# Maduino_Zero_Bluetooth_4_0_HM-13_v1_0.net
KiCad netlist of a schematic drawn in EAGLE
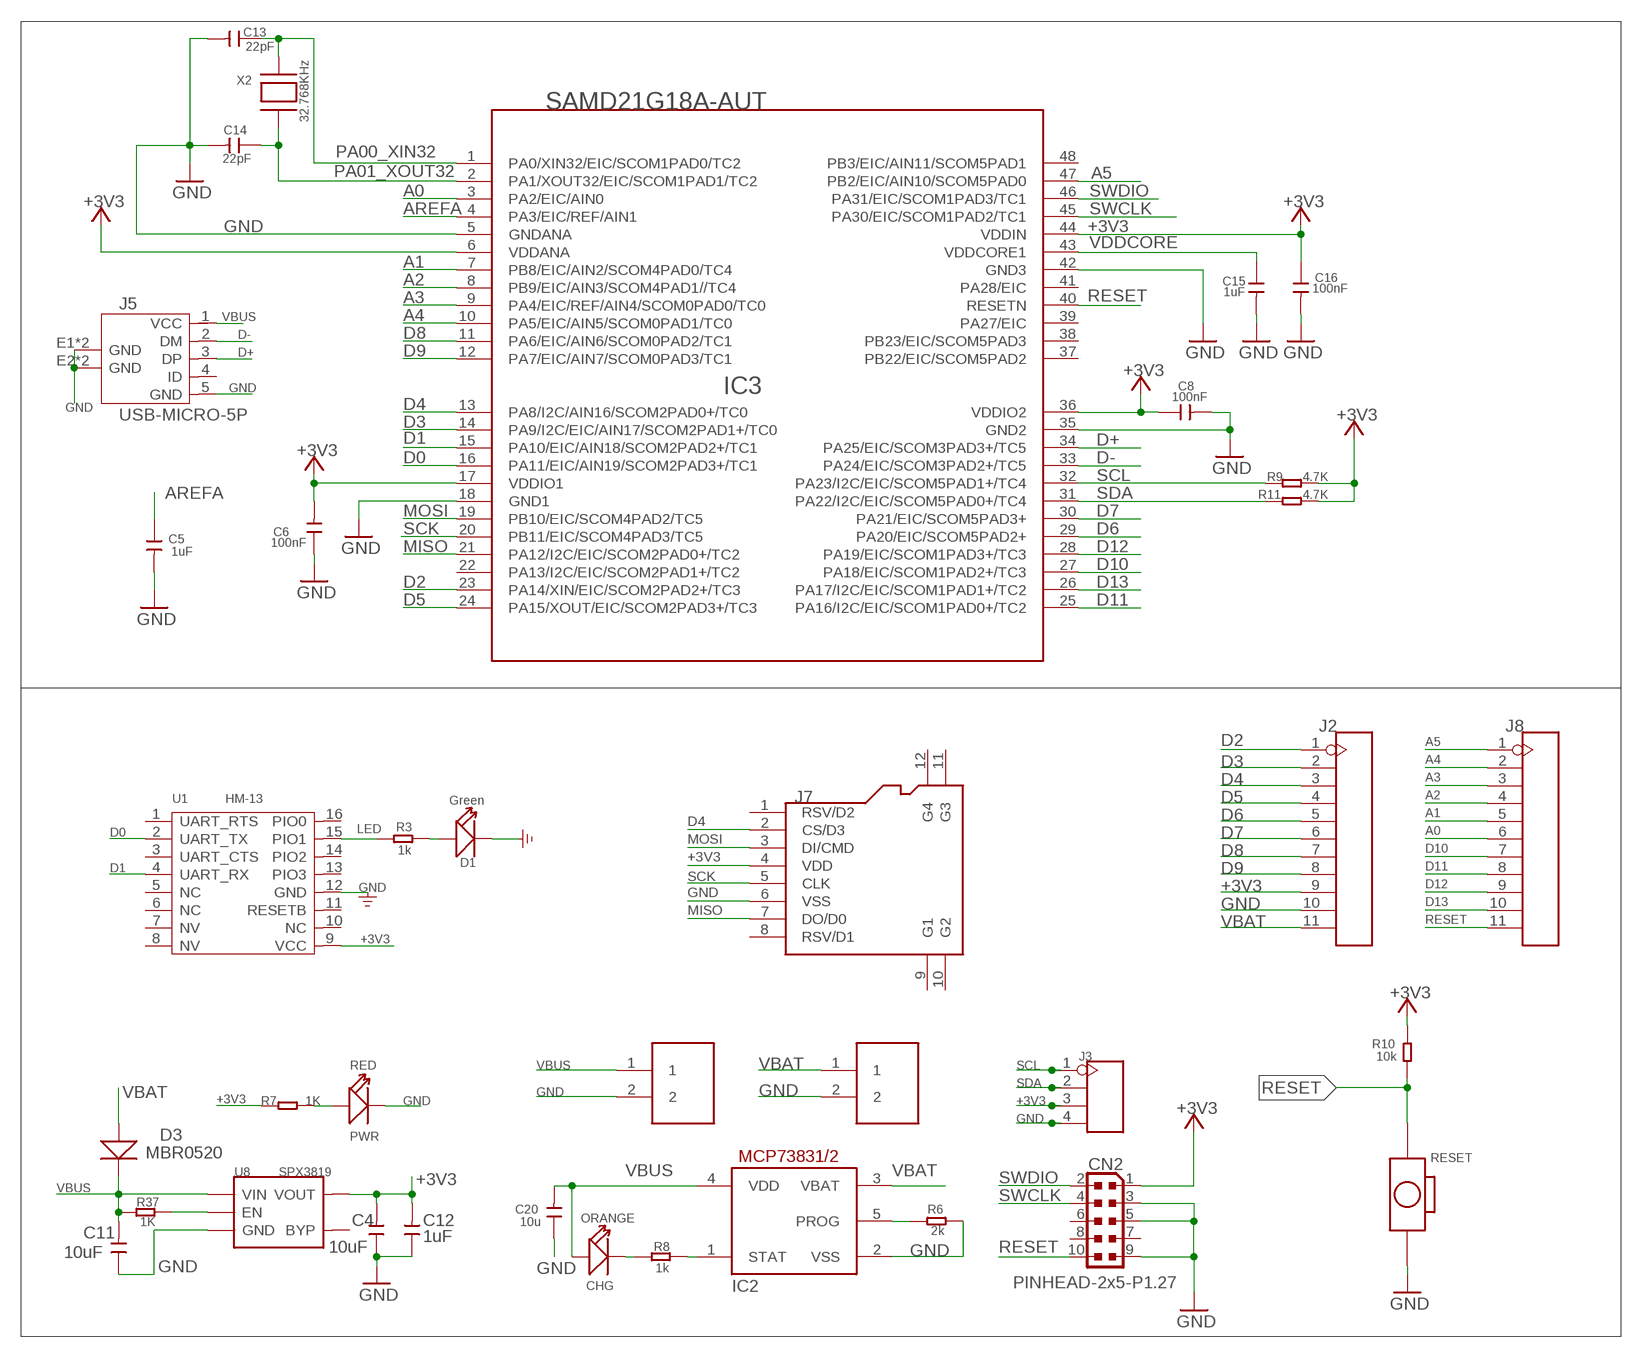
[diagram p0: schematic, sheet 1]

(export (version "E")
  (design (tool "Eeschema 10.0.6"))
  (components
    (comp (ref "C4")
      (value "10uF")
      (footprint "eagle-import:0603")
      (libsource (lib "eagle-import") (part "C-0603"))
    )
    (comp (ref "C5")
      (value "1uF")
      (footprint "eagle-import:0603")
      (libsource (lib "eagle-import") (part "C-0603"))
    )
    (comp (ref "C6")
      (value "100nF")
      (footprint "eagle-import:0603")
      (libsource (lib "eagle-import") (part "C-0603"))
    )
    (comp (ref "C8")
      (value "100nF")
      (footprint "eagle-import:0603")
      (libsource (lib "eagle-import") (part "C-0603"))
    )
    (comp (ref "C11")
      (value "10uF")
      (footprint "eagle-import:0603")
      (libsource (lib "eagle-import") (part "C-0603"))
    )
    (comp (ref "C12")
      (value "1uF")
      (footprint "eagle-import:0603")
      (libsource (lib "eagle-import") (part "C-0603"))
    )
    (comp (ref "C13")
      (value "22pF")
      (footprint "eagle-import:0603")
      (libsource (lib "eagle-import") (part "C-0603"))
    )
    (comp (ref "C14")
      (value "22pF")
      (footprint "eagle-import:0603")
      (libsource (lib "eagle-import") (part "C-0603"))
    )
    (comp (ref "C15")
      (value "1uF")
      (footprint "eagle-import:0603")
      (libsource (lib "eagle-import") (part "C-0603"))
    )
    (comp (ref "C16")
      (value "100nF")
      (footprint "eagle-import:0603")
      (libsource (lib "eagle-import") (part "C-0603"))
    )
    (comp (ref "C20")
      (value "10u")
      (footprint "eagle-import:0603")
      (libsource (lib "eagle-import") (part "C-0603"))
    )
    (comp (ref "CHG")
      (value "ORANGE")
      (footprint "eagle-import:D0603")
      (libsource (lib "eagle-import") (part "007-LED0603"))
    )
    (comp (ref "CN2")
      (value "PINHEAD-2x5-P1.27")
      (footprint "eagle-import:PINHEAD_2X05_127")
      (libsource (lib "eagle-import") (part "0171_PH127-205DF055G00AROUND-PADS"))
    )
    (comp (ref "D1")
      (value "Green")
      (footprint "eagle-import:LED-0603")
      (libsource (lib "eagle-import") (part "LED'0603'"))
    )
    (comp (ref "D3")
      (value "MBR0520")
      (footprint "eagle-import:SOD123")
      (libsource (lib "eagle-import") (part "D'1206'"))
    )
    (comp (ref "IC2")
      (value "MCP73831/OT")
      (footprint "eagle-import:SOT23-5L")
      (libsource (lib "eagle-import") (part "MCP73831/OT"))
    )
    (comp (ref "IC3")
      (value "SAMD21G18A-AUT")
      (footprint "eagle-import:TQFP48-7X7")
      (libsource (lib "eagle-import") (part "ATSAMD21G18A-AUT"))
    )
    (comp (ref "J1")
      (value "PH2.0-2P-90-DIP")
      (footprint "eagle-import:PH2.0-2P-90-DIP")
      (libsource (lib "eagle-import") (part "PH2.0-2P-90-DIP"))
    )
    (comp (ref "J2")
      (value "HEADER-11P-2.54")
      (footprint "eagle-import:11P-2.54")
      (libsource (lib "eagle-import") (part "HEADER-11P-2.54"))
    )
    (comp (ref "J3")
      (value "HEADER-4P-60/35MILROUND")
      (footprint "eagle-import:4P-65_35ROUND")
      (libsource (lib "eagle-import") (part "HEADER-4P-60/35MILROUND"))
    )
    (comp (ref "J5")
      (value "USB-MICRO-5P")
      (footprint "eagle-import:MICRO-USB-5P")
      (libsource (lib "eagle-import") (part "USB-MICRO-5P"))
    )
    (comp (ref "J6")
      (value "PH2.0-2P-90-DIP")
      (footprint "eagle-import:PH2.0-2P-90-DIP")
      (libsource (lib "eagle-import") (part "PH2.0-2P-90-DIP"))
    )
    (comp (ref "J7")
      (value "HOLDER-MICROSD-8P")
      (footprint "eagle-import:8P-SMD")
      (libsource (lib "eagle-import") (part "HOLDER-MICROSD-8P"))
    )
    (comp (ref "J8")
      (value "HEADER-11P-2.54")
      (footprint "eagle-import:11P-2.54")
      (libsource (lib "eagle-import") (part "HEADER-11P-2.54"))
    )
    (comp (ref "PWR")
      (value "RED")
      (footprint "eagle-import:LED-0603")
      (libsource (lib "eagle-import") (part "LED'0603'"))
    )
    (comp (ref "R3")
      (value "1k")
      (footprint "eagle-import:R0603")
      (libsource (lib "eagle-import") (part "R-0603"))
    )
    (comp (ref "R6")
      (value "2k")
      (footprint "eagle-import:R0603")
      (libsource (lib "eagle-import") (part "R-0603"))
    )
    (comp (ref "R7")
      (value "1K")
      (footprint "eagle-import:R0603")
      (libsource (lib "eagle-import") (part "R-0603"))
    )
    (comp (ref "R8")
      (value "1k")
      (footprint "eagle-import:R0603")
      (libsource (lib "eagle-import") (part "R-0603"))
    )
    (comp (ref "R9")
      (value "4.7K")
      (footprint "eagle-import:R0603")
      (libsource (lib "eagle-import") (part "R-0603"))
    )
    (comp (ref "R10")
      (value "10k")
      (footprint "eagle-import:R0603")
      (libsource (lib "eagle-import") (part "R-0603"))
    )
    (comp (ref "R11")
      (value "4.7K")
      (footprint "eagle-import:R0603")
      (libsource (lib "eagle-import") (part "R-0603"))
    )
    (comp (ref "R37")
      (value "1K")
      (footprint "eagle-import:R0603")
      (libsource (lib "eagle-import") (part "R-0603"))
    )
    (comp (ref "RESET")
      (value "BOTTON-2P-90D")
      (footprint "eagle-import:2P-7.62X3.56-90D")
      (libsource (lib "eagle-import") (part "BOTTON-2P-90D"))
    )
    (comp (ref "U1")
      (value "HM-13")
      (footprint "eagle-import:16P-18.5X13.5X0.8")
      (libsource (lib "eagle-import") (part "HM-11"))
    )
    (comp (ref "U8")
      (value "SPX3819")
      (footprint "eagle-import:SOT23-5")
      (libsource (lib "eagle-import") (part "SPX3819"))
    )
    (comp (ref "X2")
      (value "32.768KHz")
      (footprint "eagle-import:XTAL3215")
      (libsource (lib "eagle-import") (part "XTAL-3.2X1.5"))
    )
  )
  (nets
    (net (code "1") (name "+3V3") (class "Default")
      (node (ref "C12") (pin "2") (pinfunction "2_2") (pintype "passive"))
      (node (ref "C16") (pin "1") (pinfunction "1_1") (pintype "passive"))
      (node (ref "C4") (pin "2") (pinfunction "2_2") (pintype "passive"))
      (node (ref "C6") (pin "2") (pinfunction "2_2") (pintype "passive"))
      (node (ref "C8") (pin "1") (pinfunction "1_1") (pintype "passive"))
      (node (ref "CN2") (pin "1") (pinfunction "1_1") (pintype "passive"))
      (node (ref "IC3") (pin "17") (pinfunction "VDDIO1_17") (pintype "power_in"))
      (node (ref "IC3") (pin "36") (pinfunction "VDDIO2_36") (pintype "power_in"))
      (node (ref "IC3") (pin "44") (pinfunction "VDDIN_44") (pintype "power_in"))
      (node (ref "IC3") (pin "6") (pinfunction "VDDANA_6") (pintype "power_in"))
      (node (ref "J2") (pin "9") (pinfunction "9_9") (pintype "bidirectional"))
      (node (ref "J3") (pin "3") (pinfunction "P$3_3") (pintype "bidirectional"))
      (node (ref "J7") (pin "4") (pinfunction "VDD_4") (pintype "bidirectional"))
      (node (ref "R10") (pin "2") (pinfunction "2_2") (pintype "passive"))
      (node (ref "R11") (pin "2") (pinfunction "2_2") (pintype "passive"))
      (node (ref "R7") (pin "1") (pinfunction "1_1") (pintype "passive"))
      (node (ref "R9") (pin "2") (pinfunction "2_2") (pintype "passive"))
      (node (ref "U1") (pin "9") (pinfunction "VCC_9") (pintype "bidirectional"))
      (node (ref "U8") (pin "5") (pinfunction "VOUT_5") (pintype "bidirectional"))
    )
    (net (code "2") (name "/A0") (class "Default")
      (node (ref "IC3") (pin "3") (pinfunction "PA2/EIC/AIN0_3") (pintype "bidirectional"))
      (node (ref "J8") (pin "6") (pinfunction "6_6") (pintype "bidirectional"))
    )
    (net (code "3") (name "/A1") (class "Default")
      (node (ref "IC3") (pin "7") (pinfunction "PB8/EIC/AIN2/SCOM4PAD0/TC4_7") (pintype "bidirectional"))
      (node (ref "J8") (pin "5") (pinfunction "5_5") (pintype "bidirectional"))
    )
    (net (code "4") (name "/A2") (class "Default")
      (node (ref "IC3") (pin "8") (pinfunction "PB9/EIC/AIN3/SCOM4PAD1//TC4_8") (pintype "bidirectional"))
      (node (ref "J8") (pin "4") (pinfunction "4_4") (pintype "bidirectional"))
    )
    (net (code "5") (name "/A3") (class "Default")
      (node (ref "IC3") (pin "9") (pinfunction "PA4/EIC/REF/AIN4/SCOM0PAD0/TC0_9") (pintype "bidirectional"))
      (node (ref "J8") (pin "3") (pinfunction "3_3") (pintype "bidirectional"))
    )
    (net (code "6") (name "/A4") (class "Default")
      (node (ref "IC3") (pin "10") (pinfunction "PA5/EIC/AIN5/SCOM0PAD1/TC0_10") (pintype "bidirectional"))
      (node (ref "J8") (pin "2") (pinfunction "2_2") (pintype "bidirectional"))
    )
    (net (code "7") (name "/A5") (class "Default")
      (node (ref "IC3") (pin "47") (pinfunction "PB2/EIC/AIN10/SCOM5PAD0_47") (pintype "bidirectional"))
      (node (ref "J8") (pin "1") (pinfunction "1_1") (pintype "bidirectional"))
    )
    (net (code "8") (name "/AREFA") (class "Default")
      (node (ref "C5") (pin "1") (pinfunction "1_1") (pintype "passive"))
      (node (ref "IC3") (pin "4") (pinfunction "PA3/EIC/REF/AIN1_4") (pintype "bidirectional"))
    )
    (net (code "9") (name "/D+") (class "Default")
      (node (ref "IC3") (pin "34") (pinfunction "PA25/EIC/SCOM3PAD3+/TC5_34") (pintype "bidirectional"))
      (node (ref "J5") (pin "3") (pinfunction "DP_3") (pintype "bidirectional"))
    )
    (net (code "10") (name "/D-") (class "Default")
      (node (ref "IC3") (pin "33") (pinfunction "PA24/EIC/SCOM3PAD2+/TC5_33") (pintype "bidirectional"))
      (node (ref "J5") (pin "2") (pinfunction "DM_2") (pintype "bidirectional"))
    )
    (net (code "11") (name "/D0") (class "Default")
      (node (ref "IC3") (pin "16") (pinfunction "PA11/EIC/AIN19/SCOM2PAD3+/TC1_16") (pintype "bidirectional"))
      (node (ref "U1") (pin "2") (pinfunction "UART_TX_2") (pintype "bidirectional"))
    )
    (net (code "12") (name "/D1") (class "Default")
      (node (ref "IC3") (pin "15") (pinfunction "PA10/EIC/AIN18/SCOM2PAD2+/TC1_15") (pintype "bidirectional"))
      (node (ref "U1") (pin "4") (pinfunction "UART_RX_4") (pintype "bidirectional"))
    )
    (net (code "13") (name "/D2") (class "Default")
      (node (ref "IC3") (pin "23") (pinfunction "PA14/XIN/EIC/SCOM2PAD2+/TC3_23") (pintype "bidirectional"))
      (node (ref "J2") (pin "1") (pinfunction "1_1") (pintype "bidirectional"))
    )
    (net (code "14") (name "/D3") (class "Default")
      (node (ref "IC3") (pin "14") (pinfunction "PA9/I2C/EIC/AIN17/SCOM2PAD1+/TC0_14") (pintype "bidirectional"))
      (node (ref "J2") (pin "2") (pinfunction "2_2") (pintype "bidirectional"))
    )
    (net (code "15") (name "/D4") (class "Default")
      (node (ref "IC3") (pin "13") (pinfunction "PA8/I2C/AIN16/SCOM2PAD0+/TC0_13") (pintype "bidirectional"))
      (node (ref "J2") (pin "3") (pinfunction "3_3") (pintype "bidirectional"))
      (node (ref "J7") (pin "2") (pinfunction "CS/D3_2") (pintype "bidirectional"))
    )
    (net (code "16") (name "/D5") (class "Default")
      (node (ref "IC3") (pin "24") (pinfunction "PA15/XOUT/EIC/SCOM2PAD3+/TC3_24") (pintype "bidirectional"))
      (node (ref "J2") (pin "4") (pinfunction "4_4") (pintype "bidirectional"))
    )
    (net (code "17") (name "/D6") (class "Default")
      (node (ref "IC3") (pin "29") (pinfunction "PA20/EIC/SCOM5PAD2+_29") (pintype "bidirectional"))
      (node (ref "J2") (pin "5") (pinfunction "5_5") (pintype "bidirectional"))
    )
    (net (code "18") (name "/D7") (class "Default")
      (node (ref "IC3") (pin "30") (pinfunction "PA21/EIC/SCOM5PAD3+_30") (pintype "bidirectional"))
      (node (ref "J2") (pin "6") (pinfunction "6_6") (pintype "bidirectional"))
    )
    (net (code "19") (name "/D8") (class "Default")
      (node (ref "IC3") (pin "11") (pinfunction "PA6/EIC/AIN6/SCOM0PAD2/TC1_11") (pintype "bidirectional"))
      (node (ref "J2") (pin "7") (pinfunction "7_7") (pintype "bidirectional"))
    )
    (net (code "20") (name "/D9") (class "Default")
      (node (ref "IC3") (pin "12") (pinfunction "PA7/EIC/AIN7/SCOM0PAD3/TC1_12") (pintype "bidirectional"))
      (node (ref "J2") (pin "8") (pinfunction "8_8") (pintype "bidirectional"))
    )
    (net (code "21") (name "/D10") (class "Default")
      (node (ref "IC3") (pin "27") (pinfunction "PA18/EIC/SCOM1PAD2+/TC3_27") (pintype "bidirectional"))
      (node (ref "J8") (pin "7") (pinfunction "7_7") (pintype "bidirectional"))
    )
    (net (code "22") (name "/D11") (class "Default")
      (node (ref "IC3") (pin "25") (pinfunction "PA16/I2C/EIC/SCOM1PAD0+/TC2_25") (pintype "bidirectional"))
      (node (ref "J8") (pin "8") (pinfunction "8_8") (pintype "bidirectional"))
    )
    (net (code "23") (name "/D12") (class "Default")
      (node (ref "IC3") (pin "28") (pinfunction "PA19/EIC/SCOM1PAD3+/TC3_28") (pintype "bidirectional"))
      (node (ref "J8") (pin "9") (pinfunction "9_9") (pintype "bidirectional"))
    )
    (net (code "24") (name "/D13") (class "Default")
      (node (ref "IC3") (pin "26") (pinfunction "PA17/I2C/EIC/SCOM1PAD1+/TC2_26") (pintype "bidirectional"))
      (node (ref "J8") (pin "10") (pinfunction "10_10") (pintype "bidirectional"))
    )
    (net (code "25") (name "/LED") (class "Default")
      (node (ref "R3") (pin "1") (pinfunction "1_1") (pintype "passive"))
      (node (ref "U1") (pin "15") (pinfunction "PIO1_15") (pintype "bidirectional"))
    )
    (net (code "26") (name "/MISO") (class "Default")
      (node (ref "IC3") (pin "21") (pinfunction "PA12/I2C/EIC/SCOM2PAD0+/TC2_21") (pintype "bidirectional"))
      (node (ref "J7") (pin "7") (pinfunction "DO/D0_7") (pintype "bidirectional"))
    )
    (net (code "27") (name "/MOSI") (class "Default")
      (node (ref "IC3") (pin "19") (pinfunction "PB10/EIC/SCOM4PAD2/TC5_19") (pintype "bidirectional"))
      (node (ref "J7") (pin "3") (pinfunction "DI/CMD_3") (pintype "bidirectional"))
    )
    (net (code "28") (name "/PA00_XIN32") (class "Default")
      (node (ref "C13") (pin "1") (pinfunction "1_1") (pintype "passive"))
      (node (ref "IC3") (pin "1") (pinfunction "PA0/XIN32/EIC/SCOM1PAD0/TC2_1") (pintype "bidirectional"))
      (node (ref "X2") (pin "P$2") (pinfunction "P$2_P$2") (pintype "bidirectional"))
    )
    (net (code "29") (name "/PA01_XOUT32") (class "Default")
      (node (ref "C14") (pin "1") (pinfunction "1_1") (pintype "passive"))
      (node (ref "IC3") (pin "2") (pinfunction "PA1/XOUT32/EIC/SCOM1PAD1/TC2_2") (pintype "bidirectional"))
      (node (ref "X2") (pin "P$1") (pinfunction "P$1_P$1") (pintype "bidirectional"))
    )
    (net (code "30") (name "/SCK") (class "Default")
      (node (ref "IC3") (pin "20") (pinfunction "PB11/EIC/SCOM4PAD3/TC5_20") (pintype "bidirectional"))
      (node (ref "J7") (pin "5") (pinfunction "CLK_5") (pintype "bidirectional"))
    )
    (net (code "31") (name "/SCL") (class "Default")
      (node (ref "IC3") (pin "32") (pinfunction "PA23/I2C/EIC/SCOM5PAD1+/TC4_32") (pintype "bidirectional"))
      (node (ref "J3") (pin "1") (pinfunction "P$1_1") (pintype "bidirectional"))
      (node (ref "R9") (pin "1") (pinfunction "1_1") (pintype "passive"))
    )
    (net (code "32") (name "/SDA") (class "Default")
      (node (ref "IC3") (pin "31") (pinfunction "PA22/I2C/EIC/SCOM5PAD0+/TC4_31") (pintype "bidirectional"))
      (node (ref "J3") (pin "2") (pinfunction "P$2_2") (pintype "bidirectional"))
      (node (ref "R11") (pin "1") (pinfunction "1_1") (pintype "passive"))
    )
    (net (code "33") (name "/SWCLK") (class "Default")
      (node (ref "CN2") (pin "4") (pinfunction "4_4") (pintype "passive"))
      (node (ref "IC3") (pin "45") (pinfunction "PA30/EIC/SCOM1PAD2/TC1_45") (pintype "bidirectional"))
    )
    (net (code "34") (name "/SWDIO") (class "Default")
      (node (ref "CN2") (pin "2") (pinfunction "2_2") (pintype "passive"))
      (node (ref "IC3") (pin "46") (pinfunction "PA31/EIC/SCOM1PAD3/TC1_46") (pintype "bidirectional"))
    )
    (net (code "35") (name "/VBAT") (class "Default")
      (node (ref "D3") (pin "+") (pinfunction "+_+") (pintype "passive"))
      (node (ref "IC2") (pin "3") (pinfunction "VBAT_3") (pintype "bidirectional"))
      (node (ref "J2") (pin "11") (pinfunction "11_11") (pintype "bidirectional"))
      (node (ref "J6") (pin "1") (pinfunction "1_1") (pintype "bidirectional"))
    )
    (net (code "36") (name "/VBUS") (class "Default")
      (node (ref "C11") (pin "2") (pinfunction "2_2") (pintype "passive"))
      (node (ref "C20") (pin "2") (pinfunction "2_2") (pintype "passive"))
      (node (ref "CHG") (pin "+") (pinfunction "+_+") (pintype "passive"))
      (node (ref "D3") (pin "-") (pinfunction "-_-") (pintype "passive"))
      (node (ref "IC2") (pin "4") (pinfunction "VDD_4") (pintype "power_in"))
      (node (ref "J1") (pin "1") (pinfunction "1_1") (pintype "bidirectional"))
      (node (ref "J5") (pin "1") (pinfunction "VCC_1") (pintype "bidirectional"))
      (node (ref "R37") (pin "1") (pinfunction "1_1") (pintype "passive"))
      (node (ref "U8") (pin "1") (pinfunction "VIN_1") (pintype "bidirectional"))
    )
    (net (code "37") (name "/VDDCORE") (class "Default")
      (node (ref "C15") (pin "1") (pinfunction "1_1") (pintype "passive"))
      (node (ref "IC3") (pin "43") (pinfunction "VDDCORE1_43") (pintype "input"))
    )
    (net (code "38") (name "GND") (class "Default")
      (node (ref "C11") (pin "1") (pinfunction "1_1") (pintype "passive"))
      (node (ref "C12") (pin "1") (pinfunction "1_1") (pintype "passive"))
      (node (ref "C13") (pin "2") (pinfunction "2_2") (pintype "passive"))
      (node (ref "C14") (pin "2") (pinfunction "2_2") (pintype "passive"))
      (node (ref "C15") (pin "2") (pinfunction "2_2") (pintype "passive"))
      (node (ref "C16") (pin "2") (pinfunction "2_2") (pintype "passive"))
      (node (ref "C20") (pin "1") (pinfunction "1_1") (pintype "passive"))
      (node (ref "C4") (pin "1") (pinfunction "1_1") (pintype "passive"))
      (node (ref "C5") (pin "2") (pinfunction "2_2") (pintype "passive"))
      (node (ref "C6") (pin "1") (pinfunction "1_1") (pintype "passive"))
      (node (ref "C8") (pin "2") (pinfunction "2_2") (pintype "passive"))
      (node (ref "CN2") (pin "3") (pinfunction "3_3") (pintype "passive"))
      (node (ref "CN2") (pin "5") (pinfunction "5_5") (pintype "passive"))
      (node (ref "CN2") (pin "9") (pinfunction "9_9") (pintype "passive"))
      (node (ref "D1") (pin "-") (pinfunction "-_-") (pintype "passive"))
      (node (ref "IC2") (pin "2") (pinfunction "VSS_2") (pintype "power_in"))
      (node (ref "IC3") (pin "18") (pinfunction "GND1_18") (pintype "power_in"))
      (node (ref "IC3") (pin "35") (pinfunction "GND2_35") (pintype "power_in"))
      (node (ref "IC3") (pin "42") (pinfunction "GND3_42") (pintype "power_in"))
      (node (ref "IC3") (pin "5") (pinfunction "GNDANA_5") (pintype "power_in"))
      (node (ref "J1") (pin "2") (pinfunction "2_2") (pintype "bidirectional"))
      (node (ref "J2") (pin "10") (pinfunction "10_10") (pintype "bidirectional"))
      (node (ref "J3") (pin "4") (pinfunction "P$4_4") (pintype "bidirectional"))
      (node (ref "J5") (pin "5") (pinfunction "GND_5") (pintype "bidirectional"))
      (node (ref "J5") (pin "E1") (pinfunction "GND_E1") (pintype "bidirectional"))
      (node (ref "J5") (pin "E2") (pinfunction "GND_E2") (pintype "bidirectional"))
      (node (ref "J5") (pin "P1") (pinfunction "GND_P1") (pintype "bidirectional"))
      (node (ref "J5") (pin "P2") (pinfunction "GND_P2") (pintype "bidirectional"))
      (node (ref "J6") (pin "2") (pinfunction "2_2") (pintype "bidirectional"))
      (node (ref "J7") (pin "6") (pinfunction "VSS_6") (pintype "bidirectional"))
      (node (ref "PWR") (pin "-") (pinfunction "-_-") (pintype "passive"))
      (node (ref "R6") (pin "2") (pinfunction "2_2") (pintype "passive"))
      (node (ref "RESET") (pin "P$2") (pinfunction "2_P$2") (pintype "bidirectional"))
      (node (ref "U1") (pin "12") (pinfunction "GND_12") (pintype "bidirectional"))
      (node (ref "U8") (pin "2") (pinfunction "GND_2") (pintype "bidirectional"))
    )
    (net (code "39") (name "Net-(CHG-Pad-)") (class "Default")
      (node (ref "CHG") (pin "-") (pinfunction "-_-") (pintype "passive"))
      (node (ref "R8") (pin "1") (pinfunction "1_1") (pintype "passive"))
    )
    (net (code "40") (name "Net-(D1-Pad+)") (class "Default")
      (node (ref "D1") (pin "+") (pinfunction "+_+") (pintype "passive"))
      (node (ref "R3") (pin "2") (pinfunction "2_2") (pintype "passive"))
    )
    (net (code "41") (name "Net-(IC2-PROG)") (class "Default")
      (node (ref "IC2") (pin "5") (pinfunction "PROG_5") (pintype "input"))
      (node (ref "R6") (pin "1") (pinfunction "1_1") (pintype "passive"))
    )
    (net (code "42") (name "Net-(IC2-STAT)") (class "Default")
      (node (ref "IC2") (pin "1") (pinfunction "STAT_1") (pintype "output"))
      (node (ref "R8") (pin "2") (pinfunction "2_2") (pintype "passive"))
    )
    (net (code "43") (name "Net-(PWR-Pad+)") (class "Default")
      (node (ref "PWR") (pin "+") (pinfunction "+_+") (pintype "passive"))
      (node (ref "R7") (pin "2") (pinfunction "2_2") (pintype "passive"))
    )
    (net (code "44") (name "Net-(U8-EN)") (class "Default")
      (node (ref "R37") (pin "2") (pinfunction "2_2") (pintype "passive"))
      (node (ref "U8") (pin "3") (pinfunction "EN_3") (pintype "bidirectional"))
    )
    (net (code "45") (name "RESET") (class "Default")
      (node (ref "CN2") (pin "10") (pinfunction "10_10") (pintype "passive"))
      (node (ref "IC3") (pin "40") (pinfunction "RESETN_40") (pintype "bidirectional"))
      (node (ref "J8") (pin "11") (pinfunction "11_11") (pintype "bidirectional"))
      (node (ref "R10") (pin "1") (pinfunction "1_1") (pintype "passive"))
      (node (ref "RESET") (pin "P$1") (pinfunction "1_P$1") (pintype "bidirectional"))
    )
    (net (code "46") (name "unconnected-(CN2-Pad6)") (class "Default")
      (node (ref "CN2") (pin "6") (pinfunction "6_6") (pintype "passive"))
    )
    (net (code "47") (name "unconnected-(CN2-Pad7)") (class "Default")
      (node (ref "CN2") (pin "7") (pinfunction "7_7") (pintype "passive"))
    )
    (net (code "48") (name "unconnected-(CN2-Pad8)") (class "Default")
      (node (ref "CN2") (pin "8") (pinfunction "8_8") (pintype "passive"))
    )
    (net (code "49") (name "unconnected-(IC3-PA13{slash}I2C{slash}EIC{slash}SCOM2PAD1+{slash}TC2-Pad22)") (class "Default")
      (node (ref "IC3") (pin "22") (pinfunction "PA13/I2C/EIC/SCOM2PAD1+/TC2_22") (pintype "bidirectional"))
    )
    (net (code "50") (name "unconnected-(IC3-PA27{slash}EIC-Pad39)") (class "Default")
      (node (ref "IC3") (pin "39") (pinfunction "PA27/EIC_39") (pintype "bidirectional"))
    )
    (net (code "51") (name "unconnected-(IC3-PA28{slash}EIC-Pad41)") (class "Default")
      (node (ref "IC3") (pin "41") (pinfunction "PA28/EIC_41") (pintype "bidirectional"))
    )
    (net (code "52") (name "unconnected-(IC3-PB3{slash}EIC{slash}AIN11{slash}SCOM5PAD1-Pad48)") (class "Default")
      (node (ref "IC3") (pin "48") (pinfunction "PB3/EIC/AIN11/SCOM5PAD1_48") (pintype "bidirectional"))
    )
    (net (code "53") (name "unconnected-(IC3-PB22{slash}EIC{slash}SCOM5PAD2-Pad37)") (class "Default")
      (node (ref "IC3") (pin "37") (pinfunction "PB22/EIC/SCOM5PAD2_37") (pintype "bidirectional"))
    )
    (net (code "54") (name "unconnected-(IC3-PB23{slash}EIC{slash}SCOM5PAD3-Pad38)") (class "Default")
      (node (ref "IC3") (pin "38") (pinfunction "PB23/EIC/SCOM5PAD3_38") (pintype "bidirectional"))
    )
    (net (code "55") (name "unconnected-(J5-ID-Pad4)") (class "Default")
      (node (ref "J5") (pin "4") (pinfunction "ID_4") (pintype "bidirectional"))
    )
    (net (code "56") (name "unconnected-(J7-G1-Pad9)") (class "Default")
      (node (ref "J7") (pin "9") (pinfunction "G1_9") (pintype "bidirectional"))
    )
    (net (code "57") (name "unconnected-(J7-G2-Pad10)") (class "Default")
      (node (ref "J7") (pin "10") (pinfunction "G2_10") (pintype "bidirectional"))
    )
    (net (code "58") (name "unconnected-(J7-G3-Pad11)") (class "Default")
      (node (ref "J7") (pin "11") (pinfunction "G3_11") (pintype "bidirectional"))
    )
    (net (code "59") (name "unconnected-(J7-G4-Pad12)") (class "Default")
      (node (ref "J7") (pin "12") (pinfunction "G4_12") (pintype "bidirectional"))
    )
    (net (code "60") (name "unconnected-(J7-RSV{slash}D1-Pad8)") (class "Default")
      (node (ref "J7") (pin "8") (pinfunction "RSV/D1_8") (pintype "bidirectional"))
    )
    (net (code "61") (name "unconnected-(J7-RSV{slash}D2-Pad1)") (class "Default")
      (node (ref "J7") (pin "1") (pinfunction "RSV/D2_1") (pintype "bidirectional"))
    )
    (net (code "62") (name "unconnected-(U1-NC-Pad5)") (class "Default")
      (node (ref "U1") (pin "5") (pinfunction "NC_5") (pintype "bidirectional"))
    )
    (net (code "63") (name "unconnected-(U1-NC-Pad6)") (class "Default")
      (node (ref "U1") (pin "6") (pinfunction "NC_6") (pintype "bidirectional"))
    )
    (net (code "64") (name "unconnected-(U1-NC-Pad10)") (class "Default")
      (node (ref "U1") (pin "10") (pinfunction "NC_10") (pintype "bidirectional"))
    )
    (net (code "65") (name "unconnected-(U1-NV-Pad7)") (class "Default")
      (node (ref "U1") (pin "7") (pinfunction "NV_7") (pintype "bidirectional"))
    )
    (net (code "66") (name "unconnected-(U1-NV-Pad8)") (class "Default")
      (node (ref "U1") (pin "8") (pinfunction "NV_8") (pintype "bidirectional"))
    )
    (net (code "67") (name "unconnected-(U1-PIO0-Pad16)") (class "Default")
      (node (ref "U1") (pin "16") (pinfunction "PIO0_16") (pintype "bidirectional"))
    )
    (net (code "68") (name "unconnected-(U1-PIO2-Pad14)") (class "Default")
      (node (ref "U1") (pin "14") (pinfunction "PIO2_14") (pintype "bidirectional"))
    )
    (net (code "69") (name "unconnected-(U1-PIO3-Pad13)") (class "Default")
      (node (ref "U1") (pin "13") (pinfunction "PIO3_13") (pintype "bidirectional"))
    )
    (net (code "70") (name "unconnected-(U1-RESETB-Pad11)") (class "Default")
      (node (ref "U1") (pin "11") (pinfunction "RESETB_11") (pintype "bidirectional"))
    )
    (net (code "71") (name "unconnected-(U1-UART_CTS-Pad3)") (class "Default")
      (node (ref "U1") (pin "3") (pinfunction "UART_CTS_3") (pintype "bidirectional"))
    )
    (net (code "72") (name "unconnected-(U1-UART_RTS-Pad1)") (class "Default")
      (node (ref "U1") (pin "1") (pinfunction "UART_RTS_1") (pintype "bidirectional"))
    )
    (net (code "73") (name "unconnected-(U8-BYP-Pad4)") (class "Default")
      (node (ref "U8") (pin "4") (pinfunction "BYP_4") (pintype "bidirectional"))
    )
  )
)
